# atmega8_dip_jumpers.net
KiCad netlist of a schematic drawn in EAGLE
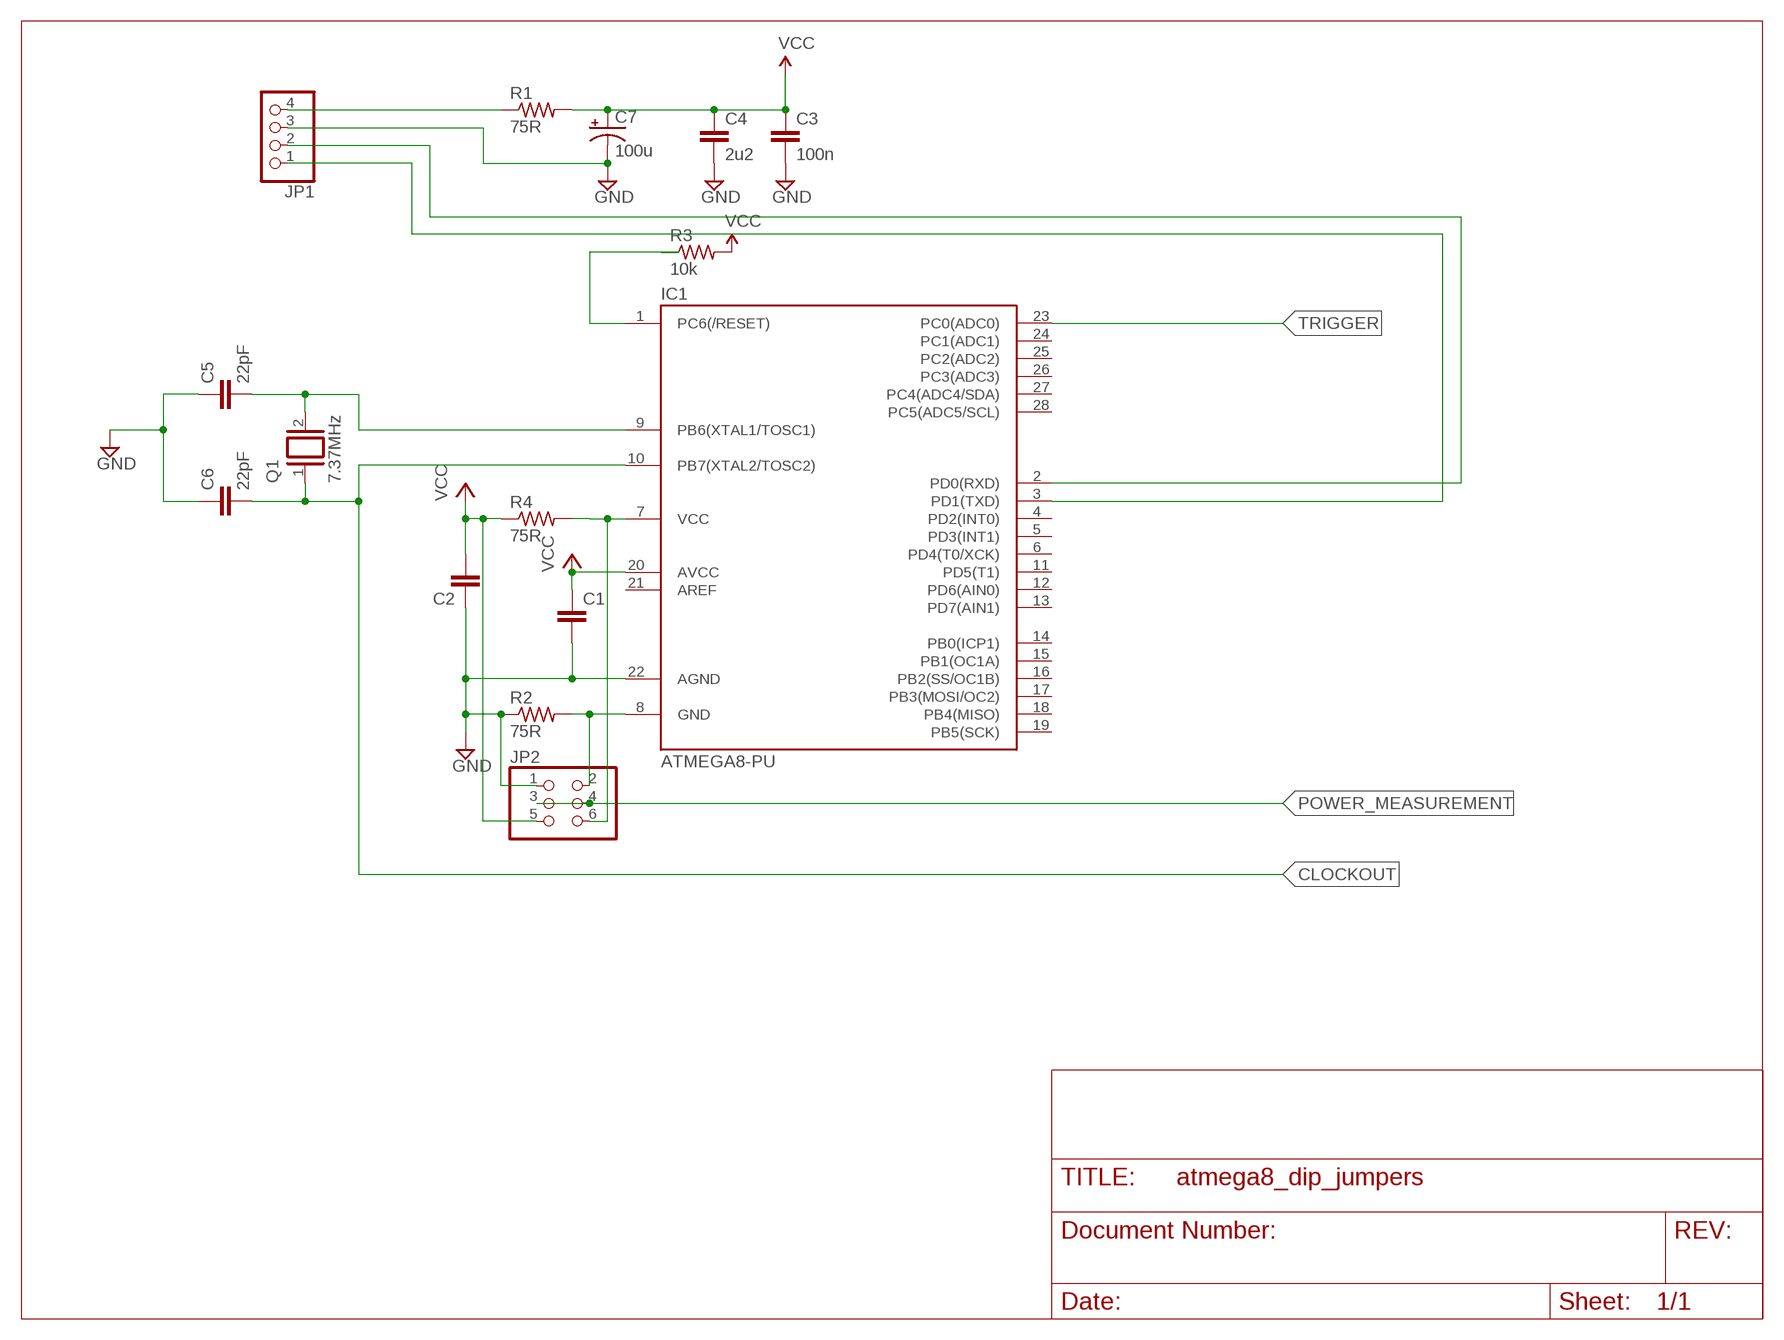
[diagram p0: schematic, sheet 1]

(export (version "E")
  (design (tool "Eeschema 10.0.6"))
  (components
    (comp (ref "C1")
      (value "C-EUC0805")
      (footprint "eagle-import:C0805")
      (libsource (lib "eagle-import") (part "C-EUC0805"))
    )
    (comp (ref "C2")
      (value "C-EUC0805")
      (footprint "eagle-import:C0805")
      (libsource (lib "eagle-import") (part "C-EUC0805"))
    )
    (comp (ref "C3")
      (value "100n")
      (footprint "eagle-import:C0805")
      (libsource (lib "eagle-import") (part "C-EUC0805"))
    )
    (comp (ref "C4")
      (value "2u2")
      (footprint "eagle-import:C0805")
      (libsource (lib "eagle-import") (part "C-EUC0805"))
    )
    (comp (ref "C5")
      (value "22pF")
      (footprint "eagle-import:C0805")
      (libsource (lib "eagle-import") (part "C-EUC0805"))
    )
    (comp (ref "C6")
      (value "22pF")
      (footprint "eagle-import:C0805")
      (libsource (lib "eagle-import") (part "C-EUC0805"))
    )
    (comp (ref "C7")
      (value "100u")
      (footprint "eagle-import:140CLH-0810")
      (libsource (lib "eagle-import") (part "CPOL-US140CLH-0810"))
    )
    (comp (ref "IC1")
      (value "ATMEGA8-PU")
      (footprint "eagle-import:DIL28-3")
      (libsource (lib "eagle-import") (part "ATMEGA8-PU"))
    )
    (comp (ref "JP1")
      (value "PINHD-1X4/90")
      (footprint "eagle-import:1X04_90")
      (libsource (lib "eagle-import") (part "PINHD-1X4/90"))
    )
    (comp (ref "JP2")
      (value "PINHD-2X3")
      (footprint "eagle-import:2X03")
      (libsource (lib "eagle-import") (part "PINHD-2X3"))
    )
    (comp (ref "Q1")
      (value "7.37MHz")
      (footprint "eagle-import:Q")
      (libsource (lib "eagle-import") (part "XTAL"))
    )
    (comp (ref "R1")
      (value "75R")
      (footprint "eagle-import:M0805")
      (libsource (lib "eagle-import") (part "R-US_M0805"))
    )
    (comp (ref "R2")
      (value "75R")
      (footprint "eagle-import:R0805")
      (libsource (lib "eagle-import") (part "resistor_R-US_R0805"))
    )
    (comp (ref "R3")
      (value "10k")
      (footprint "eagle-import:M0805")
      (libsource (lib "eagle-import") (part "R-US_M0805"))
    )
    (comp (ref "R4")
      (value "75R")
      (footprint "eagle-import:R0805")
      (libsource (lib "eagle-import") (part "resistor_R-US_R0805"))
    )
  )
  (nets
    (net (code "1") (name "CLOCKOUT") (class "Default")
      (node (ref "C6") (pin "2") (pinfunction "2_2") (pintype "passive"))
      (node (ref "IC1") (pin "10") (pinfunction "PB7(XTAL2/TOSC2)_10") (pintype "bidirectional"))
      (node (ref "Q1") (pin "1") (pinfunction "1_1") (pintype "passive"))
    )
    (net (code "2") (name "GND") (class "Default")
      (node (ref "C1") (pin "2") (pinfunction "2_2") (pintype "passive"))
      (node (ref "C2") (pin "1") (pinfunction "1_1") (pintype "passive"))
      (node (ref "C3") (pin "2") (pinfunction "2_2") (pintype "passive"))
      (node (ref "C4") (pin "2") (pinfunction "2_2") (pintype "passive"))
      (node (ref "C5") (pin "1") (pinfunction "1_1") (pintype "passive"))
      (node (ref "C6") (pin "1") (pinfunction "1_1") (pintype "passive"))
      (node (ref "C7") (pin "-") (pinfunction "-_-") (pintype "passive"))
      (node (ref "IC1") (pin "22") (pinfunction "AGND_22") (pintype "power_in"))
      (node (ref "JP1") (pin "3") (pinfunction "3_3") (pintype "passive"))
      (node (ref "JP2") (pin "1") (pinfunction "1_1") (pintype "passive"))
      (node (ref "R2") (pin "1") (pinfunction "1_1") (pintype "passive"))
    )
    (net (code "3") (name "Net-(IC1-GND)") (class "Default")
      (node (ref "IC1") (pin "8") (pinfunction "GND_8") (pintype "power_in"))
      (node (ref "JP2") (pin "2") (pinfunction "2_2") (pintype "passive"))
      (node (ref "R2") (pin "2") (pinfunction "2_2") (pintype "passive"))
    )
    (net (code "4") (name "Net-(IC1-PB6(XTAL1{slash}TOSC1))") (class "Default")
      (node (ref "C5") (pin "2") (pinfunction "2_2") (pintype "passive"))
      (node (ref "IC1") (pin "9") (pinfunction "PB6(XTAL1/TOSC1)_9") (pintype "bidirectional"))
      (node (ref "Q1") (pin "2") (pinfunction "2_2") (pintype "passive"))
    )
    (net (code "5") (name "Net-(IC1-PD0(RXD))") (class "Default")
      (node (ref "IC1") (pin "2") (pinfunction "PD0(RXD)_2") (pintype "bidirectional"))
      (node (ref "JP1") (pin "2") (pinfunction "2_2") (pintype "passive"))
    )
    (net (code "6") (name "Net-(IC1-PD1(TXD))") (class "Default")
      (node (ref "IC1") (pin "3") (pinfunction "PD1(TXD)_3") (pintype "bidirectional"))
      (node (ref "JP1") (pin "1") (pinfunction "1_1") (pintype "passive"))
    )
    (net (code "7") (name "Net-(IC1-VCC)") (class "Default")
      (node (ref "IC1") (pin "7") (pinfunction "VCC_7") (pintype "power_in"))
      (node (ref "JP2") (pin "6") (pinfunction "6_6") (pintype "passive"))
      (node (ref "R4") (pin "2") (pinfunction "2_2") (pintype "passive"))
    )
    (net (code "8") (name "Net-(JP1-Pad4)") (class "Default")
      (node (ref "JP1") (pin "4") (pinfunction "4_4") (pintype "passive"))
      (node (ref "R1") (pin "1") (pinfunction "1_1") (pintype "passive"))
    )
    (net (code "9") (name "POWER_MEASUREMENT") (class "Default")
      (node (ref "JP2") (pin "3") (pinfunction "3_3") (pintype "passive"))
      (node (ref "JP2") (pin "4") (pinfunction "4_4") (pintype "passive"))
    )
    (net (code "10") (name "TRIGGER") (class "Default")
      (node (ref "IC1") (pin "23") (pinfunction "PC0(ADC0)_23") (pintype "bidirectional"))
    )
    (net (code "11") (name "VCC") (class "Default")
      (node (ref "C1") (pin "1") (pinfunction "1_1") (pintype "passive"))
      (node (ref "C2") (pin "2") (pinfunction "2_2") (pintype "passive"))
      (node (ref "C3") (pin "1") (pinfunction "1_1") (pintype "passive"))
      (node (ref "C4") (pin "1") (pinfunction "1_1") (pintype "passive"))
      (node (ref "C7") (pin "+") (pinfunction "+_+") (pintype "passive"))
      (node (ref "IC1") (pin "20") (pinfunction "AVCC_20") (pintype "passive"))
      (node (ref "JP2") (pin "5") (pinfunction "5_5") (pintype "passive"))
      (node (ref "R1") (pin "2") (pinfunction "2_2") (pintype "passive"))
      (node (ref "R3") (pin "2") (pinfunction "2_2") (pintype "passive"))
      (node (ref "R4") (pin "1") (pinfunction "1_1") (pintype "passive"))
    )
    (net (code "12") (name "unconnected-(IC1-AREF-Pad21)") (class "Default")
      (node (ref "IC1") (pin "21") (pinfunction "AREF_21") (pintype "passive"))
    )
    (net (code "13") (name "unconnected-(IC1-PB0(ICP1)-Pad14)") (class "Default")
      (node (ref "IC1") (pin "14") (pinfunction "PB0(ICP1)_14") (pintype "bidirectional"))
    )
    (net (code "14") (name "unconnected-(IC1-PB1(OC1A)-Pad15)") (class "Default")
      (node (ref "IC1") (pin "15") (pinfunction "PB1(OC1A)_15") (pintype "bidirectional"))
    )
    (net (code "15") (name "unconnected-(IC1-PB2(SS{slash}OC1B)-Pad16)") (class "Default")
      (node (ref "IC1") (pin "16") (pinfunction "PB2(SS/OC1B)_16") (pintype "bidirectional"))
    )
    (net (code "16") (name "unconnected-(IC1-PB3(MOSI{slash}OC2)-Pad17)") (class "Default")
      (node (ref "IC1") (pin "17") (pinfunction "PB3(MOSI/OC2)_17") (pintype "bidirectional"))
    )
    (net (code "17") (name "unconnected-(IC1-PB4(MISO)-Pad18)") (class "Default")
      (node (ref "IC1") (pin "18") (pinfunction "PB4(MISO)_18") (pintype "bidirectional"))
    )
    (net (code "18") (name "unconnected-(IC1-PB5(SCK)-Pad19)") (class "Default")
      (node (ref "IC1") (pin "19") (pinfunction "PB5(SCK)_19") (pintype "bidirectional"))
    )
    (net (code "19") (name "unconnected-(IC1-PC1(ADC1)-Pad24)") (class "Default")
      (node (ref "IC1") (pin "24") (pinfunction "PC1(ADC1)_24") (pintype "bidirectional"))
    )
    (net (code "20") (name "unconnected-(IC1-PC2(ADC2)-Pad25)") (class "Default")
      (node (ref "IC1") (pin "25") (pinfunction "PC2(ADC2)_25") (pintype "bidirectional"))
    )
    (net (code "21") (name "unconnected-(IC1-PC3(ADC3)-Pad26)") (class "Default")
      (node (ref "IC1") (pin "26") (pinfunction "PC3(ADC3)_26") (pintype "bidirectional"))
    )
    (net (code "22") (name "unconnected-(IC1-PC4(ADC4{slash}SDA)-Pad27)") (class "Default")
      (node (ref "IC1") (pin "27") (pinfunction "PC4(ADC4/SDA)_27") (pintype "bidirectional"))
    )
    (net (code "23") (name "unconnected-(IC1-PC5(ADC5{slash}SCL)-Pad28)") (class "Default")
      (node (ref "IC1") (pin "28") (pinfunction "PC5(ADC5/SCL)_28") (pintype "bidirectional"))
    )
    (net (code "24") (name "unconnected-(IC1-PC6({slash}RESET)-Pad1)") (class "Default")
      (node (ref "IC1") (pin "1") (pinfunction "PC6(/RESET)_1") (pintype "bidirectional"))
    )
    (net (code "25") (name "unconnected-(IC1-PD2(INT0)-Pad4)") (class "Default")
      (node (ref "IC1") (pin "4") (pinfunction "PD2(INT0)_4") (pintype "bidirectional"))
    )
    (net (code "26") (name "unconnected-(IC1-PD3(INT1)-Pad5)") (class "Default")
      (node (ref "IC1") (pin "5") (pinfunction "PD3(INT1)_5") (pintype "bidirectional"))
    )
    (net (code "27") (name "unconnected-(IC1-PD4(T0{slash}XCK)-Pad6)") (class "Default")
      (node (ref "IC1") (pin "6") (pinfunction "PD4(T0/XCK)_6") (pintype "bidirectional"))
    )
    (net (code "28") (name "unconnected-(IC1-PD5(T1)-Pad11)") (class "Default")
      (node (ref "IC1") (pin "11") (pinfunction "PD5(T1)_11") (pintype "bidirectional"))
    )
    (net (code "29") (name "unconnected-(IC1-PD6(AIN0)-Pad12)") (class "Default")
      (node (ref "IC1") (pin "12") (pinfunction "PD6(AIN0)_12") (pintype "bidirectional"))
    )
    (net (code "30") (name "unconnected-(IC1-PD7(AIN1)-Pad13)") (class "Default")
      (node (ref "IC1") (pin "13") (pinfunction "PD7(AIN1)_13") (pintype "bidirectional"))
    )
    (net (code "31") (name "unconnected-(R3-Pad1)") (class "Default")
      (node (ref "R3") (pin "1") (pinfunction "1_1") (pintype "passive"))
    )
  )
)
